# Boost.net
KiCad netlist of a schematic drawn in Altium Designer
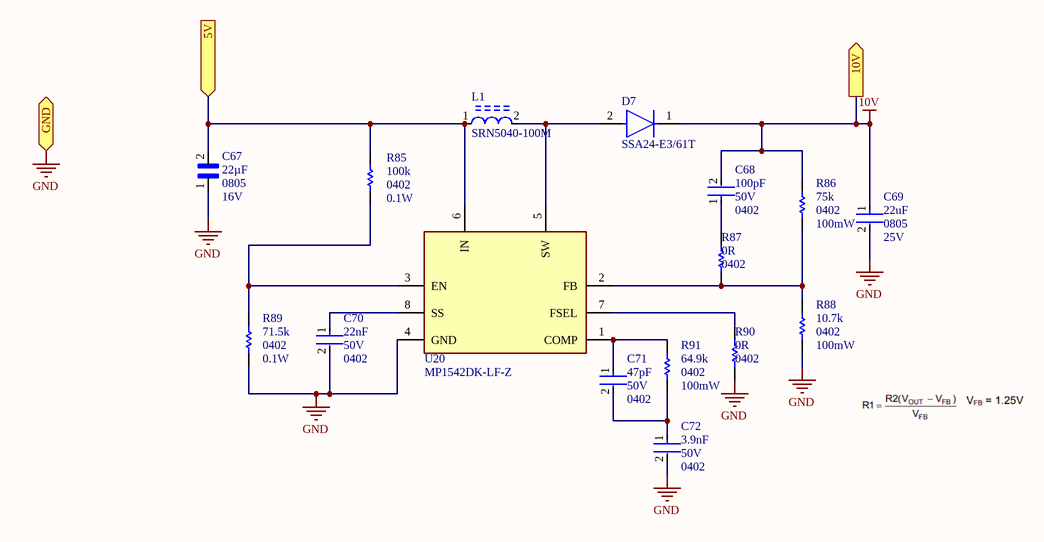
[diagram p0: Boost.SchDoc]

(export (version "E")
  (design (tool "Eeschema 10.0.6"))
  (components
    (comp (ref "C67")
      (value "22µF")
      (footprint "CAPC0805(2012)145_L")
      (description "Chip Capacitor, 22µF +/-40%, 16V, 0805, Thickness 1.45 mm")
      (fields
        (field (name "TOLERANCE") "5%")
        (field (name "CASE/PACKAGE") "0805")
        (field (name "VOLTAGE RATING") "16V")
        (field (name "Comment") "CL21A226MOQNNNE")
      )
      (libsource (lib "Digital Shovel") (part "C0805C103J3GECAUTO"))
    )
    (comp (ref "C68")
      (value "100pF")
      (footprint "FP-CC0402-MFG")
      (fields
        (field (name "PACKAGE") "0402")
        (field (name "RATING") "50V")
        (field (name "Comment") "CC0402KRX7R9BB101")
      )
      (libsource (lib "Digital Shovel") (part "11868f565c42a9108669ba33697ecf6"))
    )
    (comp (ref "C69")
      (value "22uF")
      (footprint "FP-GRM21B-0_2-e0_2_0_7-MFG")
      (fields
        (field (name "PACKAGE") "0805")
        (field (name "MANUFACTURER") "Murata")
        (field (name "VOLTAGE RATING") "25V")
        (field (name "Comment") "GRM21BR61E226ME44L")
      )
      (libsource (lib "Digital Shovel") (part "b4654b650e69147ec39a6b967a45e02"))
    )
    (comp (ref "C70")
      (value "22nF")
      (footprint "FP-GCM155-0_05-IPC_A")
      (fields
        (field (name "CASE/PACKAGE") "0402")
        (field (name "VOLTAGE RATING") "50V")
        (field (name "Comment") "GCM155R71H223KA55D")
      )
      (libsource (lib "Digital Shovel") (part "02cd4be3c70576c341d710602a673aa"))
    )
    (comp (ref "C71")
      (value "47pF")
      (footprint "FP-C0402-BB-MFG")
      (fields
        (field (name "PACKAGE") "0402")
        (field (name "RATING") "50V")
        (field (name "Comment") "C0402C470J5GACTU")
      )
      (libsource (lib "Digital Shovel") (part "b4654b650e69147ec39a6b967a45e02"))
    )
    (comp (ref "C72")
      (value "3.9nF")
      (footprint "FP-CC0402-IPC_A")
      (fields
        (field (name "CASE/PACKAGE") "0402")
        (field (name "VOLTAGE RATING") "50V")
        (field (name "Comment") "CC0402KRX7R9BB392")
      )
      (libsource (lib "Digital Shovel") (part "11868f565c42a9108669ba33697ecf6"))
    )
    (comp (ref "D7")
      (value "SSA24-E3/61T")
      (footprint "FP-95400-MFG")
      (description "Rectifier Diode, Schottky, 1 Phase, 1 Element, 2A, 40V V(RRM), Silicon, DO-214AC")
      (fields (field (name "MANUFACTURER") "Vishay"))
      (libsource (lib "Digital Shovel") (part "d7152d700b627762746794eb795d46e"))
    )
    (comp (ref "L1")
      (value "SRN5040-100M")
      (footprint "FP-SRN5040-MFG")
      (description "General Purpose Inductor, 10uH, 20%, 1 Element, Ferrite-Core, SMD, 2020")
      (fields (field (name "MANUFACTURER") "Bourns"))
      (libsource (lib "Digital Shovel") (part "94070c2b7419b78bf7304148e6ac680"))
    )
    (comp (ref "R85")
      (value "100k")
      (footprint "RESC1005X40X25LL10T10")
      (fields
        (field (name "MANUFACTURER") "KOA Speer")
        (field (name "PACKAGE") "0402")
        (field (name "MOQ") "0.1W")
        (field (name "Comment") "RK73H1ETTP1003F")
      )
      (libsource (lib "Digital Shovel") (part "RES"))
    )
    (comp (ref "R86")
      (value "75k")
      (footprint "RESC1005X40X25LL10T10")
      (fields
        (field (name "CASE/PACKAGE") "0402")
        (field (name "TOLERANCE") "1%")
        (field (name "POWER") "100mW")
        (field (name "Comment") "RK73H1ETTP7502F")
      )
      (libsource (lib "Digital Shovel") (part "RES"))
    )
    (comp (ref "R87")
      (value "0R")
      (footprint "FP-RK73Z1E-IPC_B")
      (description "Metal Glaze/thick Film, 0ohm, Surface Mount, 0402")
      (fields (field (name "PACKAGE") "0402") (field (name "Comment") "RK73Z1ETTP"))
      (libsource (lib "Digital Shovel") (part "1029c3af85768c4190bb7ad29bc67b5"))
    )
    (comp (ref "R88")
      (value "10.7k")
      (footprint "RESC1005X40X25LL10T10")
      (fields
        (field (name "POWER") "100mW")
        (field (name "TOLERANCE") "1%")
        (field (name "CASE/PACKAGE") "0402")
        (field (name "Comment") "RK73H1ETTP1072F")
      )
      (libsource (lib "Digital Shovel") (part "RES"))
    )
    (comp (ref "R89")
      (value "71.5k")
      (footprint "RESC1005X40X25LL10T10")
      (fields
        (field (name "MOUNTING") "0402")
        (field (name "PACKAGE") "0.1W")
        (field (name "Comment") "RK73H1ETTP7152F")
      )
      (libsource (lib "Digital Shovel") (part "RES"))
    )
    (comp (ref "R90")
      (value "0R")
      (footprint "FP-RK73Z1E-IPC_B")
      (description "Metal Glaze/thick Film, 0ohm, Surface Mount, 0402")
      (fields (field (name "PACKAGE") "0402") (field (name "Comment") "RK73Z1ETTP"))
      (libsource (lib "Digital Shovel") (part "1029c3af85768c4190bb7ad29bc67b5"))
    )
    (comp (ref "R91")
      (value "64.9k")
      (footprint "RESC1005X40X25LL10T10")
      (fields
        (field (name "CASE/PACKAGE") "0402")
        (field (name "POWER") "100mW")
        (field (name "TOLERANCE") "1%")
        (field (name "Comment") "RK73H1ETTP6492F")
      )
      (libsource (lib "Digital Shovel") (part "RES"))
    )
    (comp (ref "U20")
      (value "MP1542DK-LF-Z")
      (footprint "MP1542-Footprint-1")
      (description "Switching Regulator, Current-mode, 2A, 1500kHz Switching Freq-Max, PDSO8")
      (fields (field (name "MANUFACTURER") "MPS"))
      (libsource (lib "Digital Shovel") (part "MP1542"))
    )
  )
  (nets
    (net (code "1") (name "/5V") (class "Default")
      (node (ref "C67") (pin "2") (pinfunction "2_2") (pintype "passive"))
      (node (ref "L1") (pin "1") (pinfunction "1_1") (pintype "passive"))
      (node (ref "R85") (pin "2") (pinfunction "2_2") (pintype "passive"))
      (node (ref "U20") (pin "6") (pinfunction "IN_6") (pintype "passive"))
    )
    (net (code "2") (name "10V") (class "Default")
      (node (ref "C68") (pin "2") (pinfunction "2_2") (pintype "passive"))
      (node (ref "C69") (pin "1") (pinfunction "1_1") (pintype "passive"))
      (node (ref "D7") (pin "1") (pinfunction "C_1") (pintype "passive"))
      (node (ref "R86") (pin "2") (pinfunction "2_2") (pintype "passive"))
    )
    (net (code "3") (name "GND") (class "Default")
      (node (ref "C67") (pin "1") (pinfunction "1_1") (pintype "passive"))
      (node (ref "C69") (pin "2") (pinfunction "2_2") (pintype "passive"))
      (node (ref "C70") (pin "2") (pinfunction "2_2") (pintype "passive"))
      (node (ref "C72") (pin "2") (pinfunction "2_2") (pintype "passive"))
      (node (ref "R88") (pin "1") (pinfunction "1_1") (pintype "passive"))
      (node (ref "R89") (pin "1") (pinfunction "1_1") (pintype "passive"))
      (node (ref "R90") (pin "1") (pinfunction "1_1") (pintype "passive"))
      (node (ref "U20") (pin "4") (pinfunction "GND_4") (pintype "passive"))
    )
    (net (code "4") (name "Net-(C68-Pad1)") (class "Default")
      (node (ref "C68") (pin "1") (pinfunction "1_1") (pintype "passive"))
      (node (ref "R87") (pin "2") (pinfunction "2_2") (pintype "passive"))
    )
    (net (code "5") (name "Net-(C71-Pad2)") (class "Default")
      (node (ref "C71") (pin "2") (pinfunction "2_2") (pintype "passive"))
      (node (ref "C72") (pin "1") (pinfunction "1_1") (pintype "passive"))
      (node (ref "R91") (pin "1") (pinfunction "1_1") (pintype "passive"))
    )
    (net (code "6") (name "Net-(D7-A)") (class "Default")
      (node (ref "D7") (pin "2") (pinfunction "A_2") (pintype "passive"))
      (node (ref "L1") (pin "2") (pinfunction "2_2") (pintype "passive"))
      (node (ref "U20") (pin "5") (pinfunction "SW_5") (pintype "passive"))
    )
    (net (code "7") (name "Net-(U20-COMP)") (class "Default")
      (node (ref "C71") (pin "1") (pinfunction "1_1") (pintype "passive"))
      (node (ref "R91") (pin "2") (pinfunction "2_2") (pintype "passive"))
      (node (ref "U20") (pin "1") (pinfunction "COMP_1") (pintype "passive"))
    )
    (net (code "8") (name "Net-(U20-EN)") (class "Default")
      (node (ref "R85") (pin "1") (pinfunction "1_1") (pintype "passive"))
      (node (ref "R89") (pin "2") (pinfunction "2_2") (pintype "passive"))
      (node (ref "U20") (pin "3") (pinfunction "EN_3") (pintype "passive"))
    )
    (net (code "9") (name "Net-(U20-FB)") (class "Default")
      (node (ref "R86") (pin "1") (pinfunction "1_1") (pintype "passive"))
      (node (ref "R87") (pin "1") (pinfunction "1_1") (pintype "passive"))
      (node (ref "R88") (pin "2") (pinfunction "2_2") (pintype "passive"))
      (node (ref "U20") (pin "2") (pinfunction "FB_2") (pintype "passive"))
    )
    (net (code "10") (name "Net-(U20-FSEL)") (class "Default")
      (node (ref "R90") (pin "2") (pinfunction "2_2") (pintype "passive"))
      (node (ref "U20") (pin "7") (pinfunction "FSEL_7") (pintype "passive"))
    )
    (net (code "11") (name "Net-(U20-SS)") (class "Default")
      (node (ref "C70") (pin "1") (pinfunction "1_1") (pintype "passive"))
      (node (ref "U20") (pin "8") (pinfunction "SS_8") (pintype "passive"))
    )
  )
)
